# EVK-NORA-W1_SCHEM_0003_Shield_Conn.net
KiCad netlist of a schematic drawn in Altium Designer
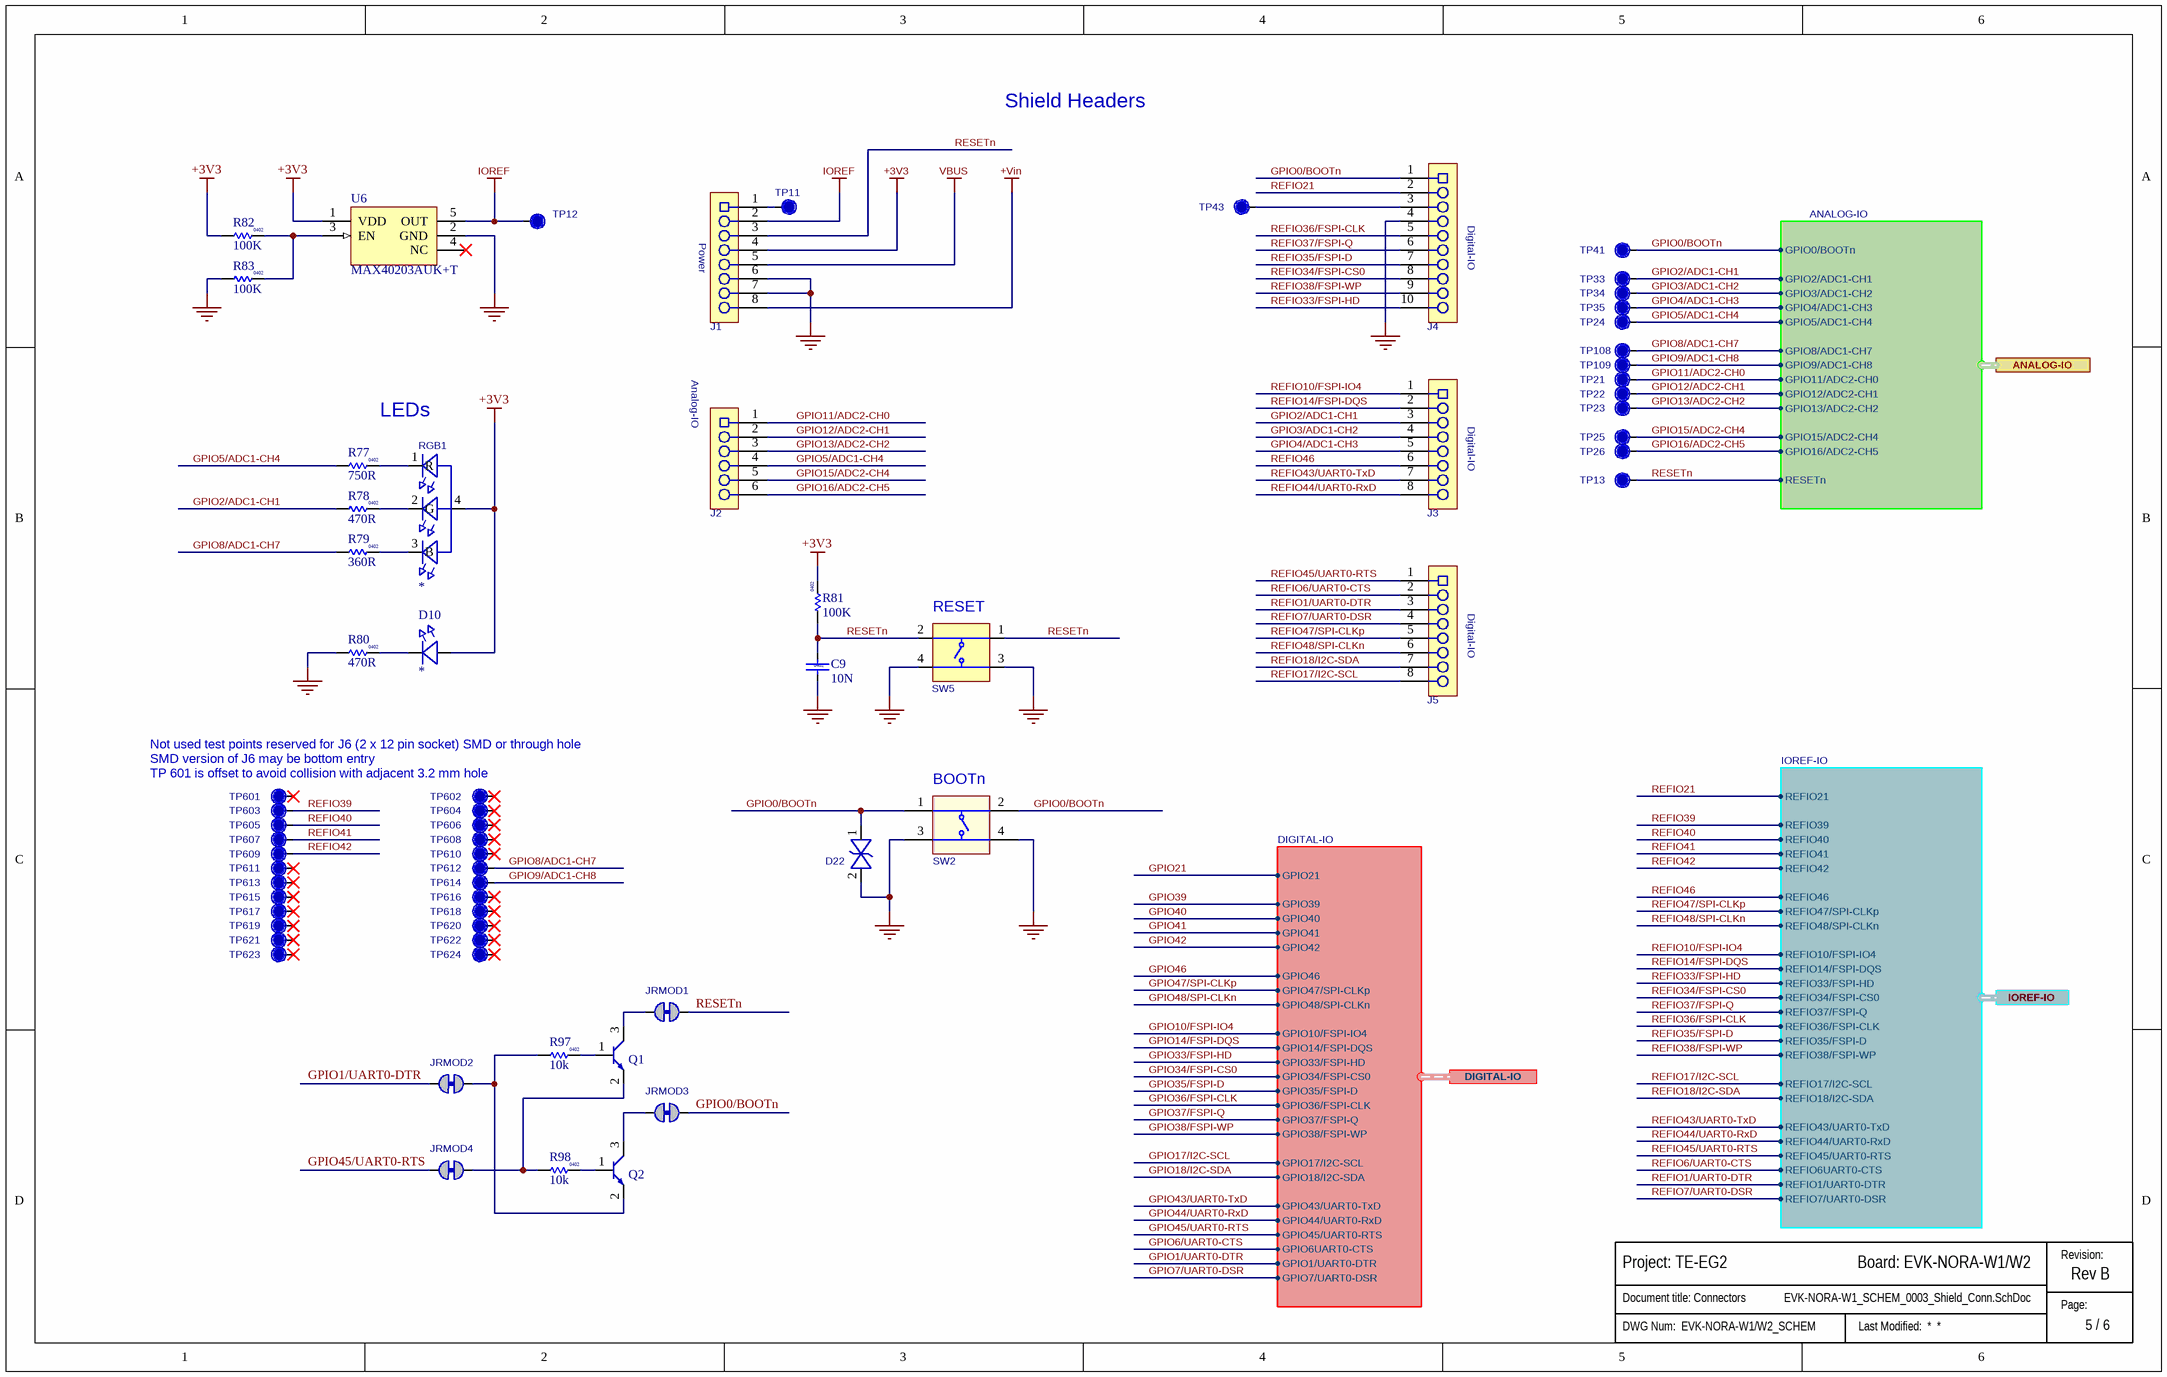
[diagram p0: EVK-NORA-W1_SCHEM_0003_Shield_Conn.SchDoc]

(export (version "E")
  (design (tool "Eeschema 10.0.6"))
  (components
    (comp (ref "C9")
      (value "10N")
      (footprint "Cap 0402")
      (description "CAP CER X7R 0402 10N 10% 16V")
      (fields
        (field (name "SIZE") "0402")
        (field (name "PART NUMBER") "UBXH01-0023025")
        (field (name "TOLERANCE") "10%")
        (field (name "EDITOR") "roland.rust")
        (field (name "RELEASED BY") "anthony.gergis")
      )
      (libsource (lib "UBX_Parts_DB_Lib") (part "Cap Chip"))
    )
    (comp (ref "D10")
      (value "UBXH11-0000018")
      (footprint "LED-0603")
      (description "LED CHIP 0603 LOW CURRENT OSRAM 0.002A GREEN 2.2V 2mA")
      (fields
        (field (name "COLOR") "*")
        (field (name "MANUFACTURER") "Osram")
        (field (name "EDITOR") "johann.furrer")
        (field (name "RELEASED BY") "martin.grasse")
      )
      (libsource (lib "UBX_Parts_DB_Lib") (part "LED_BASE"))
    )
    (comp (ref "D22")
      (value "110-00019")
      (footprint "SOD-923")
      (description "ESD9B3.3ST5G")
      (fields (field (name "MANUFACTURER") "ON Semiconductor") (field (name "VOLTAGE") "3.3V"))
      (libsource (lib "Arena_Parts_DB_Lib") (part "Diode_TVS"))
    )
    (comp (ref "J1")
      (value "130-00102")
      (footprint "SKT-0.1P-SSM-108-L-SV")
      (description "Socket Strip 0.1\" 8 Pin 1Row SMD Black")
      (fields (field (name "VOLTAGE") "572VDC"))
      (libsource (lib "Arena_Parts_DB_Lib") (part "CON-8Pin_1Row"))
    )
    (comp (ref "J2")
      (value "130-00103")
      (footprint "SKT-0.1P-SSM-106-L-SV")
      (description "Socket Strip 0.1\" 6Pin 1Row SMD Black")
      (fields (field (name "VOLTAGE") "572VDC"))
      (libsource (lib "Arena_Parts_DB_Lib") (part "CON-6Pin_1Row"))
    )
    (comp (ref "J3")
      (value "130-00102")
      (footprint "SKT-0.1P-SSM-108-L-SV")
      (description "Socket Strip 0.1\" 8 Pin 1Row SMD Black")
      (fields (field (name "VOLTAGE") "572VDC"))
      (libsource (lib "") (part "CON-8Pin_1Row_1"))
    )
    (comp (ref "J4")
      (value "130-00101")
      (footprint "SKT-0.1P-SSM-110-L-SV")
      (description "Socket Strip 0.1\" 10Pin 1Row SMD Black")
      (fields (field (name "VOLTAGE") "572VDC"))
      (libsource (lib "Arena_Parts_DB_Lib") (part "CON-10Pin_1Row"))
    )
    (comp (ref "J5")
      (value "130-00102")
      (footprint "SKT-0.1P-SSM-108-L-SV")
      (description "Socket Strip 0.1\" 8 Pin 1Row SMD Black")
      (fields (field (name "VOLTAGE") "572VDC"))
      (libsource (lib "") (part "CON-8Pin_1Row_1"))
    )
    (comp (ref "JRMOD1")
      (value "Solderbridge-ShortDNP")
      (footprint "Solderbridge-Short")
      (description "Solderbridge-Short")
      (fields (field (name "ADDED BY") "Paul B"))
      (libsource (lib "LEGACY_Rigado_AltiumLib") (part "Solderbridge-Short"))
    )
    (comp (ref "JRMOD2")
      (value "Solderbridge-ShortDNP")
      (footprint "Solderbridge-Short")
      (description "Solderbridge-Short")
      (fields (field (name "ADDED BY") "Paul B"))
      (libsource (lib "LEGACY_Rigado_AltiumLib") (part "Solderbridge-Short"))
    )
    (comp (ref "JRMOD3")
      (value "Solderbridge-ShortDNP")
      (footprint "Solderbridge-Short")
      (description "Solderbridge-Short")
      (fields (field (name "ADDED BY") "Paul B"))
      (libsource (lib "LEGACY_Rigado_AltiumLib") (part "Solderbridge-Short"))
    )
    (comp (ref "JRMOD4")
      (value "Solderbridge-ShortDNP")
      (footprint "Solderbridge-Short")
      (description "Solderbridge-Short")
      (fields (field (name "ADDED BY") "Paul B"))
      (libsource (lib "LEGACY_Rigado_AltiumLib") (part "Solderbridge-Short"))
    )
    (comp (ref "Q1")
      (value "UBXH20-0000052")
      (footprint "SOT-23")
      (description "GENERAL PURPOSE SINGLE NPN TRANSISTOR SOT-23 45V 800mA")
      (fields
        (field (name "MANUFACTURER") "ON Semiconductor")
        (field (name "EDITOR") "jaakko.jussila")
        (field (name "RELEASED BY") "alex.claville")
      )
      (libsource (lib "UBX_Parts_DB_Lib") (part "NPN_BJT"))
    )
    (comp (ref "Q2")
      (value "UBXH20-0000052")
      (footprint "SOT-23")
      (description "GENERAL PURPOSE SINGLE NPN TRANSISTOR SOT-23 45V 800mA")
      (fields
        (field (name "MANUFACTURER") "ON Semiconductor")
        (field (name "EDITOR") "jaakko.jussila")
        (field (name "RELEASED BY") "alex.claville")
      )
      (libsource (lib "UBX_Parts_DB_Lib") (part "NPN_BJT"))
    )
    (comp (ref "R77")
      (value "750R")
      (footprint "RES 0402 HD")
      (description "RES THICK FILM CHIP 0402 750R 5% 100mW")
      (fields
        (field (name "SIZE") "0402")
        (field (name "PART NUMBER") "UBXH18-0008046")
        (field (name "TOLERANCE") "5%")
        (field (name "EDITOR") "jaka.bevk")
        (field (name "RELEASED BY") "erian.bezhani")
      )
      (libsource (lib "UBX_Parts_DB_Lib") (part "Res sm"))
    )
    (comp (ref "R78")
      (value "470R")
      (footprint "RES 0402 HD")
      (description "RES THICK FILM CHIP 0402 470R 5% 100mW")
      (fields
        (field (name "SIZE") "0402")
        (field (name "PART NUMBER") "UBXH18-0008041")
        (field (name "TOLERANCE") "5%")
        (field (name "EDITOR") "roland.rust")
        (field (name "RELEASED BY") "roland.rust")
      )
      (libsource (lib "UBX_Parts_DB_Lib") (part "Res sm"))
    )
    (comp (ref "R79")
      (value "360R")
      (footprint "RES 0402 HD")
      (description "RES THICK FILM CHIP 0402 360R 1% 63mW")
      (fields
        (field (name "SIZE") "0402")
        (field (name "PART NUMBER") "UBXH18-0000216")
        (field (name "TOLERANCE") "1%")
        (field (name "EDITOR") "michael.hein")
        (field (name "RELEASED BY") "vasyl.dykyy")
      )
      (libsource (lib "UBX_Parts_DB_Lib") (part "Res sm"))
    )
    (comp (ref "R80")
      (value "470R")
      (footprint "RES 0402 HD")
      (description "RES THICK FILM CHIP 0402 470R 5% 100mW")
      (fields
        (field (name "SIZE") "0402")
        (field (name "PART NUMBER") "UBXH18-0008041")
        (field (name "TOLERANCE") "5%")
        (field (name "EDITOR") "roland.rust")
        (field (name "RELEASED BY") "roland.rust")
      )
      (libsource (lib "UBX_Parts_DB_Lib") (part "Res sm"))
    )
    (comp (ref "R81")
      (value "100K")
      (footprint "RES 0402 HD")
      (description "RES THICK FILM CHIP 0402 100K 5% 100mW")
      (fields
        (field (name "SIZE") "0402")
        (field (name "PART NUMBER") "UBXH18-0008097")
        (field (name "TOLERANCE") "5%")
        (field (name "EDITOR") "roland.rust")
        (field (name "RELEASED BY") "roland.rust")
      )
      (libsource (lib "UBX_Parts_DB_Lib") (part "Res sm"))
    )
    (comp (ref "R82")
      (value "100K")
      (footprint "RES 0402 HD")
      (description "RES THICK FILM CHIP 0402 100K 5% 100mW")
      (fields
        (field (name "SIZE") "0402")
        (field (name "PART NUMBER") "UBXH18-0008097")
        (field (name "TOLERANCE") "5%")
        (field (name "EDITOR") "roland.rust")
        (field (name "RELEASED BY") "roland.rust")
      )
      (libsource (lib "UBX_Parts_DB_Lib") (part "Res sm"))
    )
    (comp (ref "R83")
      (value "100K")
      (footprint "RES 0402 HD")
      (description "RES THICK FILM CHIP 0402 100K 5% 100mW")
      (fields
        (field (name "SIZE") "0402")
        (field (name "PART NUMBER") "UBXH18-0008097")
        (field (name "TOLERANCE") "5%")
        (field (name "EDITOR") "roland.rust")
        (field (name "RELEASED BY") "roland.rust")
      )
      (libsource (lib "UBX_Parts_DB_Lib") (part "Res sm"))
    )
    (comp (ref "R97")
      (value "10k")
      (footprint "RES 0402 HD")
      (description "Resistor 10k ohm 1% 1/16W, 0402")
      (fields
        (field (name "SIZE") "0402")
        (field (name "PART NUMBER") "180-00024")
        (field (name "POWER") "1/16W")
      )
      (libsource (lib "Arena_Parts_DB_Lib") (part "Res sm"))
    )
    (comp (ref "R98")
      (value "10k")
      (footprint "RES 0402 HD")
      (description "Resistor 10k ohm 1% 1/16W, 0402")
      (fields
        (field (name "SIZE") "0402")
        (field (name "PART NUMBER") "180-00024")
        (field (name "POWER") "1/16W")
      )
      (libsource (lib "Arena_Parts_DB_Lib") (part "Res sm"))
    )
    (comp (ref "RGB1")
      (value "115-00026")
      (footprint "LED_1616")
      (description "LED RGB SMT 0606")
      (fields (field (name "COLOR") "*") (field (name "VOLTAGE") "None"))
      (libsource (lib "Arena_Parts_DB_Lib") (part "LED_RGB_CA_4"))
    )
    (comp (ref "SW2")
      (value "135-00002")
      (footprint "SW_TACT_SMT_6mm")
      (description "Tactile Switch, SPST-NO, SMT, Actuation force = 160g, 6mm x 6mm")
      (fields (field (name "MANUFACTURER") "C&K Components") (field (name "VOLTAGE") "12VDC"))
      (libsource (lib "Arena_Parts_DB_Lib") (part "SW_TACT_SPST_4Pin"))
    )
    (comp (ref "SW5")
      (value "135-00002")
      (footprint "SW_TACT_SMT_6mm")
      (description "Tactile Switch, SPST-NO, SMT 160gf.")
      (fields (field (name "MANUFACTURER") "C&K Components") (field (name "VOLTAGE") "12VDC"))
      (libsource (lib "") (part "SW_TACT_SPST_4Pin_1"))
    )
    (comp (ref "TP11")
      (value "TP")
      (footprint "TP10R")
      (description "Testpoint, Round 1.0mm Dia")
      (fields
        (field (name "PART NUMBER") "TP10R")
        (field (name "ADDED BY") "Jeremy D")
        (field (name "CHECKED BY") "Paul B")
      )
      (libsource (lib "") (part "TP_R_1"))
    )
    (comp (ref "TP12")
      (value "TP")
      (footprint "TP10R")
      (description "Testpoint, Round 1.0mm Dia")
      (fields
        (field (name "PART NUMBER") "TP10R")
        (field (name "ADDED BY") "Jeremy D")
        (field (name "CHECKED BY") "Paul B")
      )
      (libsource (lib "") (part "TP_R_1"))
    )
    (comp (ref "TP13")
      (value "TP")
      (footprint "TP10R")
      (description "Testpoint, Round 1.0mm Dia")
      (fields
        (field (name "PART NUMBER") "TP10R")
        (field (name "ADDED BY") "Jeremy D")
        (field (name "CHECKED BY") "Paul B")
      )
      (libsource (lib "LEGACY_Rigado_AltiumLib") (part "TP_R"))
    )
    (comp (ref "TP21")
      (value "TP")
      (footprint "TP10R")
      (description "Testpoint, Round 1.0mm Dia")
      (fields
        (field (name "PART NUMBER") "TP10R")
        (field (name "ADDED BY") "Jeremy D")
        (field (name "CHECKED BY") "Paul B")
      )
      (libsource (lib "LEGACY_Rigado_AltiumLib") (part "TP_R"))
    )
    (comp (ref "TP22")
      (value "TP")
      (footprint "TP10R")
      (description "Testpoint, Round 1.0mm Dia")
      (fields
        (field (name "PART NUMBER") "TP10R")
        (field (name "ADDED BY") "Jeremy D")
        (field (name "CHECKED BY") "Paul B")
      )
      (libsource (lib "LEGACY_Rigado_AltiumLib") (part "TP_R"))
    )
    (comp (ref "TP23")
      (value "TP")
      (footprint "TP10R")
      (description "Testpoint, Round 1.0mm Dia")
      (fields
        (field (name "PART NUMBER") "TP10R")
        (field (name "ADDED BY") "Jeremy D")
        (field (name "CHECKED BY") "Paul B")
      )
      (libsource (lib "LEGACY_Rigado_AltiumLib") (part "TP_R"))
    )
    (comp (ref "TP24")
      (value "TP")
      (footprint "TP10R")
      (description "Testpoint, Round 1.0mm Dia")
      (fields
        (field (name "PART NUMBER") "TP10R")
        (field (name "ADDED BY") "Jeremy D")
        (field (name "CHECKED BY") "Paul B")
      )
      (libsource (lib "LEGACY_Rigado_AltiumLib") (part "TP_R"))
    )
    (comp (ref "TP25")
      (value "TP")
      (footprint "TP10R")
      (description "Testpoint, Round 1.0mm Dia")
      (fields
        (field (name "PART NUMBER") "TP10R")
        (field (name "ADDED BY") "Jeremy D")
        (field (name "CHECKED BY") "Paul B")
      )
      (libsource (lib "LEGACY_Rigado_AltiumLib") (part "TP_R"))
    )
    (comp (ref "TP26")
      (value "TP")
      (footprint "TP10R")
      (description "Testpoint, Round 1.0mm Dia")
      (fields
        (field (name "PART NUMBER") "TP10R")
        (field (name "ADDED BY") "Jeremy D")
        (field (name "CHECKED BY") "Paul B")
      )
      (libsource (lib "LEGACY_Rigado_AltiumLib") (part "TP_R"))
    )
    (comp (ref "TP33")
      (value "TP")
      (footprint "TP10R")
      (description "Testpoint, Round 1.0mm Dia")
      (fields
        (field (name "PART NUMBER") "TP10R")
        (field (name "ADDED BY") "Jeremy D")
        (field (name "CHECKED BY") "Paul B")
      )
      (libsource (lib "LEGACY_Rigado_AltiumLib") (part "TP_R"))
    )
    (comp (ref "TP34")
      (value "TP")
      (footprint "TP10R")
      (description "Testpoint, Round 1.0mm Dia")
      (fields
        (field (name "PART NUMBER") "TP10R")
        (field (name "ADDED BY") "Jeremy D")
        (field (name "CHECKED BY") "Paul B")
      )
      (libsource (lib "LEGACY_Rigado_AltiumLib") (part "TP_R"))
    )
    (comp (ref "TP35")
      (value "TP")
      (footprint "TP10R")
      (description "Testpoint, Round 1.0mm Dia")
      (fields
        (field (name "PART NUMBER") "TP10R")
        (field (name "ADDED BY") "Jeremy D")
        (field (name "CHECKED BY") "Paul B")
      )
      (libsource (lib "LEGACY_Rigado_AltiumLib") (part "TP_R"))
    )
    (comp (ref "TP41")
      (value "TP")
      (footprint "TP10R")
      (description "Testpoint, Round 1.0mm Dia")
      (fields
        (field (name "PART NUMBER") "TP10R")
        (field (name "ADDED BY") "Jeremy D")
        (field (name "CHECKED BY") "Paul B")
      )
      (libsource (lib "LEGACY_Rigado_AltiumLib") (part "TP_R"))
    )
    (comp (ref "TP43")
      (value "TP")
      (footprint "TP10R")
      (description "Testpoint, Round 1.0mm Dia")
      (fields
        (field (name "PART NUMBER") "TP10R")
        (field (name "ADDED BY") "Jeremy D")
        (field (name "CHECKED BY") "Paul B")
      )
      (libsource (lib "LEGACY_Rigado_AltiumLib") (part "TP_R"))
    )
    (comp (ref "TP108")
      (value "TP")
      (footprint "TP10R")
      (description "Testpoint, Round 1.0mm Dia")
      (fields
        (field (name "PART NUMBER") "TP10R")
        (field (name "ADDED BY") "Jeremy D")
        (field (name "CHECKED BY") "Paul B")
      )
      (libsource (lib "LEGACY_Rigado_AltiumLib") (part "TP_R"))
    )
    (comp (ref "TP109")
      (value "TP")
      (footprint "TP10R")
      (description "Testpoint, Round 1.0mm Dia")
      (fields
        (field (name "PART NUMBER") "TP10R")
        (field (name "ADDED BY") "Jeremy D")
        (field (name "CHECKED BY") "Paul B")
      )
      (libsource (lib "LEGACY_Rigado_AltiumLib") (part "TP_R"))
    )
    (comp (ref "TP601")
      (value "TP")
      (footprint "TP10R")
      (description "Testpoint, Round 1.0mm Dia")
      (fields
        (field (name "PART NUMBER") "TP10R")
        (field (name "ADDED BY") "Jeremy D")
        (field (name "CHECKED BY") "Paul B")
      )
      (libsource (lib "LEGACY_Rigado_AltiumLib") (part "TP_R"))
    )
    (comp (ref "TP602")
      (value "TP")
      (footprint "TP10R")
      (description "Testpoint, Round 1.0mm Dia")
      (fields
        (field (name "PART NUMBER") "TP10R")
        (field (name "ADDED BY") "Jeremy D")
        (field (name "CHECKED BY") "Paul B")
      )
      (libsource (lib "LEGACY_Rigado_AltiumLib") (part "TP_R"))
    )
    (comp (ref "TP603")
      (value "TP")
      (footprint "TP10R")
      (description "Testpoint, Round 1.0mm Dia")
      (fields
        (field (name "PART NUMBER") "TP10R")
        (field (name "ADDED BY") "Jeremy D")
        (field (name "CHECKED BY") "Paul B")
      )
      (libsource (lib "LEGACY_Rigado_AltiumLib") (part "TP_R"))
    )
    (comp (ref "TP604")
      (value "TP")
      (footprint "TP10R")
      (description "Testpoint, Round 1.0mm Dia")
      (fields
        (field (name "PART NUMBER") "TP10R")
        (field (name "ADDED BY") "Jeremy D")
        (field (name "CHECKED BY") "Paul B")
      )
      (libsource (lib "LEGACY_Rigado_AltiumLib") (part "TP_R"))
    )
    (comp (ref "TP605")
      (value "TP")
      (footprint "TP10R")
      (description "Testpoint, Round 1.0mm Dia")
      (fields
        (field (name "PART NUMBER") "TP10R")
        (field (name "ADDED BY") "Jeremy D")
        (field (name "CHECKED BY") "Paul B")
      )
      (libsource (lib "LEGACY_Rigado_AltiumLib") (part "TP_R"))
    )
    (comp (ref "TP606")
      (value "TP")
      (footprint "TP10R")
      (description "Testpoint, Round 1.0mm Dia")
      (fields
        (field (name "PART NUMBER") "TP10R")
        (field (name "ADDED BY") "Jeremy D")
        (field (name "CHECKED BY") "Paul B")
      )
      (libsource (lib "LEGACY_Rigado_AltiumLib") (part "TP_R"))
    )
    (comp (ref "TP607")
      (value "TP")
      (footprint "TP10R")
      (description "Testpoint, Round 1.0mm Dia")
      (fields
        (field (name "PART NUMBER") "TP10R")
        (field (name "ADDED BY") "Jeremy D")
        (field (name "CHECKED BY") "Paul B")
      )
      (libsource (lib "LEGACY_Rigado_AltiumLib") (part "TP_R"))
    )
    (comp (ref "TP608")
      (value "TP")
      (footprint "TP10R")
      (description "Testpoint, Round 1.0mm Dia")
      (fields
        (field (name "PART NUMBER") "TP10R")
        (field (name "ADDED BY") "Jeremy D")
        (field (name "CHECKED BY") "Paul B")
      )
      (libsource (lib "LEGACY_Rigado_AltiumLib") (part "TP_R"))
    )
    (comp (ref "TP609")
      (value "TP")
      (footprint "TP10R")
      (description "Testpoint, Round 1.0mm Dia")
      (fields
        (field (name "PART NUMBER") "TP10R")
        (field (name "ADDED BY") "Jeremy D")
        (field (name "CHECKED BY") "Paul B")
      )
      (libsource (lib "LEGACY_Rigado_AltiumLib") (part "TP_R"))
    )
    (comp (ref "TP610")
      (value "TP")
      (footprint "TP10R")
      (description "Testpoint, Round 1.0mm Dia")
      (fields
        (field (name "PART NUMBER") "TP10R")
        (field (name "ADDED BY") "Jeremy D")
        (field (name "CHECKED BY") "Paul B")
      )
      (libsource (lib "LEGACY_Rigado_AltiumLib") (part "TP_R"))
    )
    (comp (ref "TP611")
      (value "TP")
      (footprint "TP10R")
      (description "Testpoint, Round 1.0mm Dia")
      (fields
        (field (name "PART NUMBER") "TP10R")
        (field (name "ADDED BY") "Jeremy D")
        (field (name "CHECKED BY") "Paul B")
      )
      (libsource (lib "LEGACY_Rigado_AltiumLib") (part "TP_R"))
    )
    (comp (ref "TP612")
      (value "TP")
      (footprint "TP10R")
      (description "Testpoint, Round 1.0mm Dia")
      (fields
        (field (name "PART NUMBER") "TP10R")
        (field (name "ADDED BY") "Jeremy D")
        (field (name "CHECKED BY") "Paul B")
      )
      (libsource (lib "LEGACY_Rigado_AltiumLib") (part "TP_R"))
    )
    (comp (ref "TP613")
      (value "TP")
      (footprint "TP10R")
      (description "Testpoint, Round 1.0mm Dia")
      (fields
        (field (name "PART NUMBER") "TP10R")
        (field (name "ADDED BY") "Jeremy D")
        (field (name "CHECKED BY") "Paul B")
      )
      (libsource (lib "LEGACY_Rigado_AltiumLib") (part "TP_R"))
    )
    (comp (ref "TP614")
      (value "TP")
      (footprint "TP10R")
      (description "Testpoint, Round 1.0mm Dia")
      (fields
        (field (name "PART NUMBER") "TP10R")
        (field (name "ADDED BY") "Jeremy D")
        (field (name "CHECKED BY") "Paul B")
      )
      (libsource (lib "LEGACY_Rigado_AltiumLib") (part "TP_R"))
    )
    (comp (ref "TP615")
      (value "TP")
      (footprint "TP10R")
      (description "Testpoint, Round 1.0mm Dia")
      (fields
        (field (name "PART NUMBER") "TP10R")
        (field (name "ADDED BY") "Jeremy D")
        (field (name "CHECKED BY") "Paul B")
      )
      (libsource (lib "LEGACY_Rigado_AltiumLib") (part "TP_R"))
    )
    (comp (ref "TP616")
      (value "TP")
      (footprint "TP10R")
      (description "Testpoint, Round 1.0mm Dia")
      (fields
        (field (name "PART NUMBER") "TP10R")
        (field (name "ADDED BY") "Jeremy D")
        (field (name "CHECKED BY") "Paul B")
      )
      (libsource (lib "LEGACY_Rigado_AltiumLib") (part "TP_R"))
    )
    (comp (ref "TP617")
      (value "TP")
      (footprint "TP10R")
      (description "Testpoint, Round 1.0mm Dia")
      (fields
        (field (name "PART NUMBER") "TP10R")
        (field (name "ADDED BY") "Jeremy D")
        (field (name "CHECKED BY") "Paul B")
      )
      (libsource (lib "LEGACY_Rigado_AltiumLib") (part "TP_R"))
    )
    (comp (ref "TP618")
      (value "TP")
      (footprint "TP10R")
      (description "Testpoint, Round 1.0mm Dia")
      (fields
        (field (name "PART NUMBER") "TP10R")
        (field (name "ADDED BY") "Jeremy D")
        (field (name "CHECKED BY") "Paul B")
      )
      (libsource (lib "LEGACY_Rigado_AltiumLib") (part "TP_R"))
    )
    (comp (ref "TP619")
      (value "TP")
      (footprint "TP10R")
      (description "Testpoint, Round 1.0mm Dia")
      (fields
        (field (name "PART NUMBER") "TP10R")
        (field (name "ADDED BY") "Jeremy D")
        (field (name "CHECKED BY") "Paul B")
      )
      (libsource (lib "LEGACY_Rigado_AltiumLib") (part "TP_R"))
    )
    (comp (ref "TP620")
      (value "TP")
      (footprint "TP10R")
      (description "Testpoint, Round 1.0mm Dia")
      (fields
        (field (name "PART NUMBER") "TP10R")
        (field (name "ADDED BY") "Jeremy D")
        (field (name "CHECKED BY") "Paul B")
      )
      (libsource (lib "LEGACY_Rigado_AltiumLib") (part "TP_R"))
    )
    (comp (ref "TP621")
      (value "TP")
      (footprint "TP10R")
      (description "Testpoint, Round 1.0mm Dia")
      (fields
        (field (name "PART NUMBER") "TP10R")
        (field (name "ADDED BY") "Jeremy D")
        (field (name "CHECKED BY") "Paul B")
      )
      (libsource (lib "LEGACY_Rigado_AltiumLib") (part "TP_R"))
    )
    (comp (ref "TP622")
      (value "TP")
      (footprint "TP10R")
      (description "Testpoint, Round 1.0mm Dia")
      (fields
        (field (name "PART NUMBER") "TP10R")
        (field (name "ADDED BY") "Jeremy D")
        (field (name "CHECKED BY") "Paul B")
      )
      (libsource (lib "LEGACY_Rigado_AltiumLib") (part "TP_R"))
    )
    (comp (ref "TP623")
      (value "TP")
      (footprint "TP10R")
      (description "Testpoint, Round 1.0mm Dia")
      (fields
        (field (name "PART NUMBER") "TP10R")
        (field (name "ADDED BY") "Jeremy D")
        (field (name "CHECKED BY") "Paul B")
      )
      (libsource (lib "LEGACY_Rigado_AltiumLib") (part "TP_R"))
    )
    (comp (ref "TP624")
      (value "TP")
      (footprint "TP10R")
      (description "Testpoint, Round 1.0mm Dia")
      (fields
        (field (name "PART NUMBER") "TP10R")
        (field (name "ADDED BY") "Jeremy D")
        (field (name "CHECKED BY") "Paul B")
      )
      (libsource (lib "LEGACY_Rigado_AltiumLib") (part "TP_R"))
    )
    (comp (ref "U6")
      (value "265-00058")
      (footprint "SOT-23-5")
      (description "Ideal Diode - OR Controller Source Selector Switch P-Channel 1:1 SOT-23-5")
      (fields (field (name "VOLTAGE") "5.5V") (field (name "MANUFACTURER PART NUMBER 1") "MAX40203AUK+T"))
      (libsource (lib "Arena_Parts_DB_Lib") (part "MAX40203AUK"))
    )
  )
  (nets
    (net (code "4") (name "+3V3") (class "Default")
      (node (ref "D10") (pin "2") (pinfunction "A_2") (pintype "passive"))
      (node (ref "J1") (pin "4") (pintype "passive"))
      (node (ref "R81") (pin "2") (pinfunction "2_2") (pintype "passive"))
      (node (ref "R82") (pin "1") (pinfunction "1_1") (pintype "passive"))
      (node (ref "RGB1") (pin "4") (pinfunction "A_4") (pintype "passive"))
      (node (ref "U6") (pin "1") (pinfunction "VDD_1") (pintype "power_in"))
    )
    (net (code "5") (name "+Vin") (class "Default") (node (ref "J1") (pin "8") (pintype "passive")))
    (net (code "6") (name "/GPIO0{slash}BOOTn") (class "Default")
      (node (ref "D22") (pin "1") (pintype "passive"))
      (node (ref "J4") (pin "1") (pintype "passive"))
      (node (ref "JRMOD3") (pin "1") (pinfunction "1_1") (pintype "passive"))
      (node (ref "SW2") (pin "1") (pinfunction "1_1") (pintype "passive"))
      (node (ref "SW2") (pin "2") (pinfunction "2_2") (pintype "passive"))
      (node (ref "TP41") (pin "1") (pintype "passive"))
    )
    (net (code "7") (name "/GPIO1{slash}UART0-DTR") (class "Default")
      (node (ref "JRMOD2") (pin "2") (pinfunction "2_2") (pintype "passive"))
    )
    (net (code "8") (name "/GPIO2{slash}ADC1-CH1") (class "Default")
      (node (ref "J3") (pin "3") (pintype "passive"))
      (node (ref "R78") (pin "1") (pinfunction "1_1") (pintype "passive"))
      (node (ref "TP33") (pin "1") (pintype "passive"))
    )
    (net (code "9") (name "/GPIO3{slash}ADC1-CH2") (class "Default")
      (node (ref "J3") (pin "4") (pintype "passive"))
      (node (ref "TP34") (pin "1") (pintype "passive"))
    )
    (net (code "10") (name "/GPIO4{slash}ADC1-CH3") (class "Default")
      (node (ref "J3") (pin "5") (pintype "passive"))
      (node (ref "TP35") (pin "1") (pintype "passive"))
    )
    (net (code "11") (name "/GPIO5{slash}ADC1-CH4") (class "Default")
      (node (ref "J2") (pin "4") (pinfunction "4_4") (pintype "passive"))
      (node (ref "R77") (pin "1") (pinfunction "1_1") (pintype "passive"))
      (node (ref "TP24") (pin "1") (pintype "passive"))
    )
    (net (code "14") (name "/GPIO8{slash}ADC1-CH7") (class "Default")
      (node (ref "R79") (pin "1") (pinfunction "1_1") (pintype "passive"))
      (node (ref "TP108") (pin "1") (pintype "passive"))
      (node (ref "TP612") (pin "1") (pintype "passive"))
    )
    (net (code "15") (name "/GPIO9{slash}ADC1-CH8") (class "Default")
      (node (ref "TP109") (pin "1") (pintype "passive"))
      (node (ref "TP614") (pin "1") (pintype "passive"))
    )
    (net (code "17") (name "/GPIO11{slash}ADC2-CH0") (class "Default")
      (node (ref "J2") (pin "1") (pinfunction "1_1") (pintype "passive"))
      (node (ref "TP21") (pin "1") (pintype "passive"))
    )
    (net (code "18") (name "/GPIO12{slash}ADC2-CH1") (class "Default")
      (node (ref "J2") (pin "2") (pinfunction "2_2") (pintype "passive"))
      (node (ref "TP22") (pin "1") (pintype "passive"))
    )
    (net (code "19") (name "/GPIO13{slash}ADC2-CH2") (class "Default")
      (node (ref "J2") (pin "3") (pinfunction "3_3") (pintype "passive"))
      (node (ref "TP23") (pin "1") (pintype "passive"))
    )
    (net (code "21") (name "/GPIO15{slash}ADC2-CH4") (class "Default")
      (node (ref "J2") (pin "5") (pinfunction "5_5") (pintype "passive"))
      (node (ref "TP25") (pin "1") (pintype "passive"))
    )
    (net (code "22") (name "/GPIO16{slash}ADC2-CH5") (class "Default")
      (node (ref "J2") (pin "6") (pinfunction "6_6") (pintype "passive"))
      (node (ref "TP26") (pin "1") (pintype "passive"))
    )
    (net (code "38") (name "/GPIO45{slash}UART0-RTS") (class "Default")
      (node (ref "JRMOD4") (pin "2") (pinfunction "2_2") (pintype "passive"))
    )
    (net (code "42") (name "/REFIO1{slash}UART0-DTR") (class "Default")
      (node (ref "J5") (pin "3") (pintype "passive"))
    )
    (net (code "43") (name "/REFIO6{slash}UART0-CTS") (class "Default")
      (node (ref "J5") (pin "2") (pintype "passive"))
    )
    (net (code "44") (name "/REFIO7{slash}UART0-DSR") (class "Default")
      (node (ref "J5") (pin "4") (pintype "passive"))
    )
    (net (code "45") (name "/REFIO10{slash}FSPI-IO4") (class "Default")
      (node (ref "J3") (pin "1") (pintype "passive"))
    )
    (net (code "46") (name "/REFIO14{slash}FSPI-DQS") (class "Default")
      (node (ref "J3") (pin "2") (pintype "passive"))
    )
    (net (code "47") (name "/REFIO17{slash}I2C-SCL") (class "Default")
      (node (ref "J5") (pin "8") (pintype "passive"))
    )
    (net (code "48") (name "/REFIO18{slash}I2C-SDA") (class "Default")
      (node (ref "J5") (pin "7") (pintype "passive"))
    )
    (net (code "49") (name "/REFIO21") (class "Default") (node (ref "J4") (pin "2") (pintype "passive")))
    (net (code "50") (name "/REFIO33{slash}FSPI-HD") (class "Default")
      (node (ref "J4") (pin "10") (pintype "passive"))
    )
    (net (code "51") (name "/REFIO34{slash}FSPI-CS0") (class "Default")
      (node (ref "J4") (pin "8") (pintype "passive"))
    )
    (net (code "52") (name "/REFIO35{slash}FSPI-D") (class "Default")
      (node (ref "J4") (pin "7") (pintype "passive"))
    )
    (net (code "53") (name "/REFIO36{slash}FSPI-CLK") (class "Default")
      (node (ref "J4") (pin "5") (pintype "passive"))
    )
    (net (code "54") (name "/REFIO37{slash}FSPI-Q") (class "Default")
      (node (ref "J4") (pin "6") (pintype "passive"))
    )
    (net (code "55") (name "/REFIO38{slash}FSPI-WP") (class "Default")
      (node (ref "J4") (pin "9") (pintype "passive"))
    )
    (net (code "56") (name "/REFIO39") (class "Default") (node (ref "TP603") (pin "1") (pintype "passive")))
    (net (code "57") (name "/REFIO40") (class "Default") (node (ref "TP605") (pin "1") (pintype "passive")))
    (net (code "58") (name "/REFIO41") (class "Default") (node (ref "TP607") (pin "1") (pintype "passive")))
    (net (code "59") (name "/REFIO42") (class "Default") (node (ref "TP609") (pin "1") (pintype "passive")))
    (net (code "60") (name "/REFIO43{slash}UART0-TxD") (class "Default")
      (node (ref "J3") (pin "7") (pintype "passive"))
    )
    (net (code "61") (name "/REFIO44{slash}UART0-RxD") (class "Default")
      (node (ref "J3") (pin "8") (pintype "passive"))
    )
    (net (code "62") (name "/REFIO45{slash}UART0-RTS") (class "Default")
      (node (ref "J5") (pin "1") (pintype "passive"))
    )
    (net (code "63") (name "/REFIO46") (class "Default") (node (ref "J3") (pin "6") (pintype "passive")))
    (net (code "64") (name "/REFIO47{slash}SPI-CLKp") (class "Default")
      (node (ref "J5") (pin "5") (pintype "passive"))
    )
    (net (code "65") (name "/REFIO48{slash}SPI-CLKn") (class "Default")
      (node (ref "J5") (pin "6") (pintype "passive"))
    )
    (net (code "66") (name "/RESETn") (class "Default")
      (node (ref "C9") (pin "1") (pinfunction "1_1") (pintype "passive"))
      (node (ref "J1") (pin "3") (pintype "passive"))
      (node (ref "JRMOD1") (pin "1") (pinfunction "1_1") (pintype "passive"))
      (node (ref "R81") (pin "1") (pinfunction "1_1") (pintype "passive"))
      (node (ref "SW5") (pin "1") (pinfunction "T1_1") (pintype "passive"))
      (node (ref "SW5") (pin "2") (pinfunction "T2_2") (pintype "passive"))
      (node (ref "TP13") (pin "1") (pintype "passive"))
    )
    (net (code "70") (name "GND") (class "Default")
      (node (ref "C9") (pin "2") (pinfunction "2_2") (pintype "passive"))
      (node (ref "D22") (pin "2") (pintype "passive"))
      (node (ref "J1") (pin "6") (pintype "passive"))
      (node (ref "J1") (pin "7") (pintype "passive"))
      (node (ref "J4") (pin "4") (pintype "passive"))
      (node (ref "R80") (pin "1") (pinfunction "1_1") (pintype "passive"))
      (node (ref "R83") (pin "1") (pinfunction "1_1") (pintype "passive"))
      (node (ref "SW2") (pin "3") (pinfunction "3_3") (pintype "passive"))
      (node (ref "SW2") (pin "4") (pinfunction "4_4") (pintype "passive"))
      (node (ref "SW5") (pin "3") (pinfunction "T3_3") (pintype "passive"))
      (node (ref "SW5") (pin "4") (pinfunction "T3_4") (pintype "passive"))
      (node (ref "U6") (pin "2") (pinfunction "GND_2") (pintype "power_in"))
    )
    (net (code "71") (name "IOREF") (class "Default")
      (node (ref "J1") (pin "2") (pintype "passive"))
      (node (ref "TP12") (pin "1") (pintype "passive"))
      (node (ref "U6") (pin "5") (pinfunction "OUT_5") (pintype "power_in"))
    )
    (net (code "72") (name "Net-(D10-C)") (class "Default")
      (node (ref "D10") (pin "1") (pinfunction "C_1") (pintype "passive"))
      (node (ref "R80") (pin "2") (pinfunction "2_2") (pintype "passive"))
    )
    (net (code "73") (name "Net-(J1-Pad1)") (class "Default")
      (node (ref "J1") (pin "1") (pintype "passive"))
      (node (ref "TP11") (pin "1") (pintype "passive"))
    )
    (net (code "74") (name "Net-(J4-Pad3)") (class "Default")
      (node (ref "J4") (pin "3") (pintype "passive"))
      (node (ref "TP43") (pin "1") (pintype "passive"))
    )
    (net (code "75") (name "Net-(Q1-B)") (class "Default")
      (node (ref "Q1") (pin "1") (pinfunction "B_1") (pintype "passive"))
      (node (ref "R97") (pin "2") (pinfunction "2_2") (pintype "passive"))
    )
    (net (code "76") (name "Net-(Q1-C)") (class "Default")
      (node (ref "JRMOD1") (pin "2") (pinfunction "2_2") (pintype "passive"))
      (node (ref "Q1") (pin "3") (pinfunction "C_3") (pintype "passive"))
    )
    (net (code "77") (name "Net-(Q1-E)") (class "Default")
      (node (ref "JRMOD4") (pin "1") (pinfunction "1_1") (pintype "passive"))
      (node (ref "Q1") (pin "2") (pinfunction "E_2") (pintype "passive"))
      (node (ref "R98") (pin "1") (pinfunction "1_1") (pintype "passive"))
    )
    (net (code "78") (name "Net-(Q2-B)") (class "Default")
      (node (ref "Q2") (pin "1") (pinfunction "B_1") (pintype "passive"))
      (node (ref "R98") (pin "2") (pinfunction "2_2") (pintype "passive"))
    )
    (net (code "79") (name "Net-(Q2-C)") (class "Default")
      (node (ref "JRMOD3") (pin "2") (pinfunction "2_2") (pintype "passive"))
      (node (ref "Q2") (pin "3") (pinfunction "C_3") (pintype "passive"))
    )
    (net (code "80") (name "Net-(Q2-E)") (class "Default")
      (node (ref "JRMOD2") (pin "1") (pinfunction "1_1") (pintype "passive"))
      (node (ref "Q2") (pin "2") (pinfunction "E_2") (pintype "passive"))
      (node (ref "R97") (pin "1") (pinfunction "1_1") (pintype "passive"))
    )
    (net (code "81") (name "Net-(RGB1-B)") (class "Default")
      (node (ref "R79") (pin "2") (pinfunction "2_2") (pintype "passive"))
      (node (ref "RGB1") (pin "3") (pinfunction "B_3") (pintype "passive"))
    )
    (net (code "82") (name "Net-(RGB1-G)") (class "Default")
      (node (ref "R78") (pin "2") (pinfunction "2_2") (pintype "passive"))
      (node (ref "RGB1") (pin "2") (pinfunction "G_2") (pintype "passive"))
    )
    (net (code "83") (name "Net-(RGB1-R)") (class "Default")
      (node (ref "R77") (pin "2") (pinfunction "2_2") (pintype "passive"))
      (node (ref "RGB1") (pin "1") (pinfunction "R_1") (pintype "passive"))
    )
    (net (code "84") (name "Net-(U6-EN)") (class "Default")
      (node (ref "R82") (pin "2") (pinfunction "2_2") (pintype "passive"))
      (node (ref "R83") (pin "2") (pinfunction "2_2") (pintype "passive"))
      (node (ref "U6") (pin "3") (pinfunction "EN_3") (pintype "input"))
    )
    (net (code "85") (name "VBUS") (class "Default") (node (ref "J1") (pin "5") (pintype "passive")))
    (net (code "86") (name "unconnected-(TP601-Pad1)") (class "Default")
      (node (ref "TP601") (pin "1") (pintype "passive+no_connect"))
    )
    (net (code "87") (name "unconnected-(TP602-Pad1)") (class "Default")
      (node (ref "TP602") (pin "1") (pintype "passive+no_connect"))
    )
    (net (code "88") (name "unconnected-(TP604-Pad1)") (class "Default")
      (node (ref "TP604") (pin "1") (pintype "passive+no_connect"))
    )
    (net (code "89") (name "unconnected-(TP606-Pad1)") (class "Default")
      (node (ref "TP606") (pin "1") (pintype "passive+no_connect"))
    )
    (net (code "90") (name "unconnected-(TP608-Pad1)") (class "Default")
      (node (ref "TP608") (pin "1") (pintype "passive+no_connect"))
    )
    (net (code "91") (name "unconnected-(TP610-Pad1)") (class "Default")
      (node (ref "TP610") (pin "1") (pintype "passive+no_connect"))
    )
    (net (code "92") (name "unconnected-(TP611-Pad1)") (class "Default")
      (node (ref "TP611") (pin "1") (pintype "passive+no_connect"))
    )
    (net (code "93") (name "unconnected-(TP613-Pad1)") (class "Default")
      (node (ref "TP613") (pin "1") (pintype "passive+no_connect"))
    )
    (net (code "94") (name "unconnected-(TP615-Pad1)") (class "Default")
      (node (ref "TP615") (pin "1") (pintype "passive+no_connect"))
    )
    (net (code "95") (name "unconnected-(TP616-Pad1)") (class "Default")
      (node (ref "TP616") (pin "1") (pintype "passive+no_connect"))
    )
    (net (code "96") (name "unconnected-(TP617-Pad1)") (class "Default")
      (node (ref "TP617") (pin "1") (pintype "passive+no_connect"))
    )
    (net (code "97") (name "unconnected-(TP618-Pad1)") (class "Default")
      (node (ref "TP618") (pin "1") (pintype "passive+no_connect"))
    )
    (net (code "98") (name "unconnected-(TP619-Pad1)") (class "Default")
      (node (ref "TP619") (pin "1") (pintype "passive+no_connect"))
    )
    (net (code "99") (name "unconnected-(TP620-Pad1)") (class "Default")
      (node (ref "TP620") (pin "1") (pintype "passive+no_connect"))
    )
    (net (code "100") (name "unconnected-(TP621-Pad1)") (class "Default")
      (node (ref "TP621") (pin "1") (pintype "passive+no_connect"))
    )
    (net (code "101") (name "unconnected-(TP622-Pad1)") (class "Default")
      (node (ref "TP622") (pin "1") (pintype "passive+no_connect"))
    )
    (net (code "102") (name "unconnected-(TP623-Pad1)") (class "Default")
      (node (ref "TP623") (pin "1") (pintype "passive+no_connect"))
    )
    (net (code "103") (name "unconnected-(TP624-Pad1)") (class "Default")
      (node (ref "TP624") (pin "1") (pintype "passive+no_connect"))
    )
    (net (code "104") (name "unconnected-(U6-NC-Pad4)") (class "Default")
      (node (ref "U6") (pin "4") (pinfunction "NC_4") (pintype "passive+no_connect"))
    )
  )
)
